# letter_i.net
KiCad netlist of a schematic drawn in EAGLE
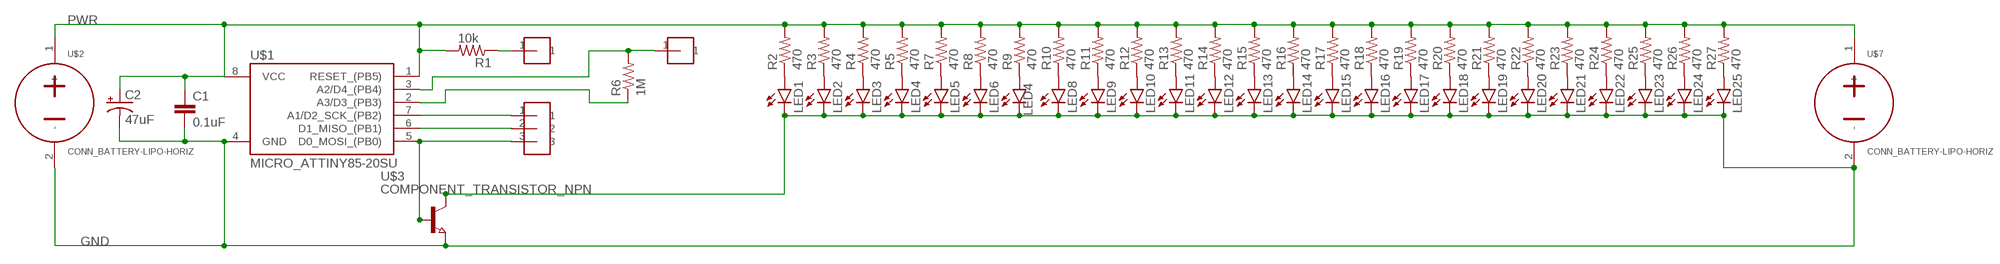
[diagram p0: schematic, sheet 1]

(export (version "E")
  (design (tool "Eeschema 10.0.6"))
  (components
    (comp (ref "C1")
      (value "0.1uF")
      (footprint "eagle-import:0805")
      (libsource (lib "eagle-import") (part "COMPONENT_CAP-0805"))
    )
    (comp (ref "C2")
      (value "47uF")
      (footprint "eagle-import:CAP_RADIAL_CAN_10MM")
      (libsource (lib "eagle-import") (part "COMPONENT_CAP_POL-6.3MM"))
    )
    (comp (ref "LED1")
      (value "LED-0805")
      (footprint "eagle-import:CHIP-LED0805")
      (libsource (lib "eagle-import") (part "LED-0805"))
    )
    (comp (ref "LED2")
      (value "LED-0805")
      (footprint "eagle-import:CHIP-LED0805")
      (libsource (lib "eagle-import") (part "LED-0805"))
    )
    (comp (ref "LED3")
      (value "LED-0805")
      (footprint "eagle-import:CHIP-LED0805")
      (libsource (lib "eagle-import") (part "LED-0805"))
    )
    (comp (ref "LED4")
      (value "LED-0805")
      (footprint "eagle-import:CHIP-LED0805")
      (libsource (lib "eagle-import") (part "LED-0805"))
    )
    (comp (ref "LED5")
      (value "LED-0805")
      (footprint "eagle-import:CHIP-LED0805")
      (libsource (lib "eagle-import") (part "LED-0805"))
    )
    (comp (ref "LED6")
      (value "LED-0805")
      (footprint "eagle-import:CHIP-LED0805")
      (libsource (lib "eagle-import") (part "LED-0805"))
    )
    (comp (ref "LED7")
      (value "LED-0805")
      (footprint "eagle-import:CHIP-LED0805")
      (libsource (lib "eagle-import") (part "LED-0805"))
    )
    (comp (ref "LED8")
      (value "LED-0805")
      (footprint "eagle-import:CHIP-LED0805")
      (libsource (lib "eagle-import") (part "LED-0805"))
    )
    (comp (ref "LED9")
      (value "LED-0805")
      (footprint "eagle-import:CHIP-LED0805")
      (libsource (lib "eagle-import") (part "LED-0805"))
    )
    (comp (ref "LED10")
      (value "LED-0805")
      (footprint "eagle-import:CHIP-LED0805")
      (libsource (lib "eagle-import") (part "LED-0805"))
    )
    (comp (ref "LED11")
      (value "LED-0805")
      (footprint "eagle-import:CHIP-LED0805")
      (libsource (lib "eagle-import") (part "LED-0805"))
    )
    (comp (ref "LED12")
      (value "LED-0805")
      (footprint "eagle-import:CHIP-LED0805")
      (libsource (lib "eagle-import") (part "LED-0805"))
    )
    (comp (ref "LED13")
      (value "LED-0805")
      (footprint "eagle-import:CHIP-LED0805")
      (libsource (lib "eagle-import") (part "LED-0805"))
    )
    (comp (ref "LED14")
      (value "LED-0805")
      (footprint "eagle-import:CHIP-LED0805")
      (libsource (lib "eagle-import") (part "LED-0805"))
    )
    (comp (ref "LED15")
      (value "LED-0805")
      (footprint "eagle-import:CHIP-LED0805")
      (libsource (lib "eagle-import") (part "LED-0805"))
    )
    (comp (ref "LED16")
      (value "LED-0805")
      (footprint "eagle-import:CHIP-LED0805")
      (libsource (lib "eagle-import") (part "LED-0805"))
    )
    (comp (ref "LED17")
      (value "LED-0805")
      (footprint "eagle-import:CHIP-LED0805")
      (libsource (lib "eagle-import") (part "LED-0805"))
    )
    (comp (ref "LED18")
      (value "LED-0805")
      (footprint "eagle-import:CHIP-LED0805")
      (libsource (lib "eagle-import") (part "LED-0805"))
    )
    (comp (ref "LED19")
      (value "LED-0805")
      (footprint "eagle-import:CHIP-LED0805")
      (libsource (lib "eagle-import") (part "LED-0805"))
    )
    (comp (ref "LED20")
      (value "LED-0805")
      (footprint "eagle-import:CHIP-LED0805")
      (libsource (lib "eagle-import") (part "LED-0805"))
    )
    (comp (ref "LED21")
      (value "LED-0805")
      (footprint "eagle-import:CHIP-LED0805")
      (libsource (lib "eagle-import") (part "LED-0805"))
    )
    (comp (ref "LED22")
      (value "LED-0805")
      (footprint "eagle-import:CHIP-LED0805")
      (libsource (lib "eagle-import") (part "LED-0805"))
    )
    (comp (ref "LED23")
      (value "LED-0805")
      (footprint "eagle-import:CHIP-LED0805")
      (libsource (lib "eagle-import") (part "LED-0805"))
    )
    (comp (ref "LED24")
      (value "LED-0805")
      (footprint "eagle-import:CHIP-LED0805")
      (libsource (lib "eagle-import") (part "LED-0805"))
    )
    (comp (ref "LED25")
      (value "LED-0805")
      (footprint "eagle-import:CHIP-LED0805")
      (libsource (lib "eagle-import") (part "LED-0805"))
    )
    (comp (ref "R1")
      (value "10k")
      (footprint "eagle-import:0805")
      (libsource (lib "eagle-import") (part "COMPONENT_RESISTOR-0805"))
    )
    (comp (ref "R2")
      (value "470")
      (footprint "eagle-import:0805")
      (libsource (lib "eagle-import") (part "COMPONENT_RESISTOR-0805"))
    )
    (comp (ref "R3")
      (value "470")
      (footprint "eagle-import:0805")
      (libsource (lib "eagle-import") (part "COMPONENT_RESISTOR-0805"))
    )
    (comp (ref "R4")
      (value "470")
      (footprint "eagle-import:0805")
      (libsource (lib "eagle-import") (part "COMPONENT_RESISTOR-0805"))
    )
    (comp (ref "R5")
      (value "470")
      (footprint "eagle-import:0805")
      (libsource (lib "eagle-import") (part "COMPONENT_RESISTOR-0805"))
    )
    (comp (ref "R6")
      (value "1M")
      (footprint "eagle-import:0805")
      (libsource (lib "eagle-import") (part "COMPONENT_RESISTOR-0805"))
    )
    (comp (ref "R7")
      (value "470")
      (footprint "eagle-import:0805")
      (libsource (lib "eagle-import") (part "COMPONENT_RESISTOR-0805"))
    )
    (comp (ref "R8")
      (value "470")
      (footprint "eagle-import:0805")
      (libsource (lib "eagle-import") (part "COMPONENT_RESISTOR-0805"))
    )
    (comp (ref "R9")
      (value "470")
      (footprint "eagle-import:0805")
      (libsource (lib "eagle-import") (part "COMPONENT_RESISTOR-0805"))
    )
    (comp (ref "R10")
      (value "470")
      (footprint "eagle-import:0805")
      (libsource (lib "eagle-import") (part "COMPONENT_RESISTOR-0805"))
    )
    (comp (ref "R11")
      (value "470")
      (footprint "eagle-import:0805")
      (libsource (lib "eagle-import") (part "COMPONENT_RESISTOR-0805"))
    )
    (comp (ref "R12")
      (value "470")
      (footprint "eagle-import:0805")
      (libsource (lib "eagle-import") (part "COMPONENT_RESISTOR-0805"))
    )
    (comp (ref "R13")
      (value "470")
      (footprint "eagle-import:0805")
      (libsource (lib "eagle-import") (part "COMPONENT_RESISTOR-0805"))
    )
    (comp (ref "R14")
      (value "470")
      (footprint "eagle-import:0805")
      (libsource (lib "eagle-import") (part "COMPONENT_RESISTOR-0805"))
    )
    (comp (ref "R15")
      (value "470")
      (footprint "eagle-import:0805")
      (libsource (lib "eagle-import") (part "COMPONENT_RESISTOR-0805"))
    )
    (comp (ref "R16")
      (value "470")
      (footprint "eagle-import:0805")
      (libsource (lib "eagle-import") (part "COMPONENT_RESISTOR-0805"))
    )
    (comp (ref "R17")
      (value "470")
      (footprint "eagle-import:0805")
      (libsource (lib "eagle-import") (part "COMPONENT_RESISTOR-0805"))
    )
    (comp (ref "R18")
      (value "470")
      (footprint "eagle-import:0805")
      (libsource (lib "eagle-import") (part "COMPONENT_RESISTOR-0805"))
    )
    (comp (ref "R19")
      (value "470")
      (footprint "eagle-import:0805")
      (libsource (lib "eagle-import") (part "COMPONENT_RESISTOR-0805"))
    )
    (comp (ref "R20")
      (value "470")
      (footprint "eagle-import:0805")
      (libsource (lib "eagle-import") (part "COMPONENT_RESISTOR-0805"))
    )
    (comp (ref "R21")
      (value "470")
      (footprint "eagle-import:0805")
      (libsource (lib "eagle-import") (part "COMPONENT_RESISTOR-0805"))
    )
    (comp (ref "R22")
      (value "470")
      (footprint "eagle-import:0805")
      (libsource (lib "eagle-import") (part "COMPONENT_RESISTOR-0805"))
    )
    (comp (ref "R23")
      (value "470")
      (footprint "eagle-import:0805")
      (libsource (lib "eagle-import") (part "COMPONENT_RESISTOR-0805"))
    )
    (comp (ref "R24")
      (value "470")
      (footprint "eagle-import:0805")
      (libsource (lib "eagle-import") (part "COMPONENT_RESISTOR-0805"))
    )
    (comp (ref "R25")
      (value "470")
      (footprint "eagle-import:0805")
      (libsource (lib "eagle-import") (part "COMPONENT_RESISTOR-0805"))
    )
    (comp (ref "R26")
      (value "470")
      (footprint "eagle-import:0805")
      (libsource (lib "eagle-import") (part "COMPONENT_RESISTOR-0805"))
    )
    (comp (ref "R27")
      (value "470")
      (footprint "eagle-import:0805")
      (libsource (lib "eagle-import") (part "COMPONENT_RESISTOR-0805"))
    )
    (comp (ref "U$1")
      (value "MICRO_ATTINY85-20SU")
      (footprint "eagle-import:SOIC8")
      (libsource (lib "eagle-import") (part "MICRO_ATTINY85-20SU"))
    )
    (comp (ref "U$2")
      (value "CONN_BATTERY-LIPO-HORIZ")
      (footprint "eagle-import:JST-PH-2-SMT-RA")
      (libsource (lib "eagle-import") (part "CONN_BATTERY-LIPO-HORIZ"))
    )
    (comp (ref "U$3")
      (value "COMPONENT_TRANSISTOR_NPN")
      (footprint "eagle-import:SOT23")
      (libsource (lib "eagle-import") (part "COMPONENT_TRANSISTOR_NPN"))
    )
    (comp (ref "U$4")
      (value "HEADER-1-TESTPOINT")
      (footprint "eagle-import:TESTPOINT-1")
      (libsource (lib "eagle-import") (part "HEADER-1-TESTPOINT"))
    )
    (comp (ref "U$5")
      (value "HEADER-1-TESTPOINT")
      (footprint "eagle-import:TESTPOINT-1")
      (libsource (lib "eagle-import") (part "HEADER-1-TESTPOINT"))
    )
    (comp (ref "U$6")
      (value "HEADER-3-TESTPOINT")
      (footprint "eagle-import:TESTPOINT-3")
      (libsource (lib "eagle-import") (part "HEADER-3-TESTPOINT"))
    )
    (comp (ref "U$7")
      (value "CONN_BATTERY-LIPO-HORIZ")
      (footprint "eagle-import:JST-PH-2-SMT-RA")
      (libsource (lib "eagle-import") (part "CONN_BATTERY-LIPO-HORIZ"))
    )
  )
  (nets
    (net (code "1") (name "/GND") (class "Default")
      (node (ref "C1") (pin "2") (pinfunction "2_2") (pintype "passive"))
      (node (ref "C2") (pin "-") (pinfunction "-_-") (pintype "passive"))
      (node (ref "LED1") (pin "C") (pinfunction "C_C") (pintype "passive"))
      (node (ref "LED10") (pin "C") (pinfunction "C_C") (pintype "passive"))
      (node (ref "LED11") (pin "C") (pinfunction "C_C") (pintype "passive"))
      (node (ref "LED12") (pin "C") (pinfunction "C_C") (pintype "passive"))
      (node (ref "LED13") (pin "C") (pinfunction "C_C") (pintype "passive"))
      (node (ref "LED14") (pin "C") (pinfunction "C_C") (pintype "passive"))
      (node (ref "LED15") (pin "C") (pinfunction "C_C") (pintype "passive"))
      (node (ref "LED16") (pin "C") (pinfunction "C_C") (pintype "passive"))
      (node (ref "LED17") (pin "C") (pinfunction "C_C") (pintype "passive"))
      (node (ref "LED18") (pin "C") (pinfunction "C_C") (pintype "passive"))
      (node (ref "LED19") (pin "C") (pinfunction "C_C") (pintype "passive"))
      (node (ref "LED2") (pin "C") (pinfunction "C_C") (pintype "passive"))
      (node (ref "LED20") (pin "C") (pinfunction "C_C") (pintype "passive"))
      (node (ref "LED21") (pin "C") (pinfunction "C_C") (pintype "passive"))
      (node (ref "LED22") (pin "C") (pinfunction "C_C") (pintype "passive"))
      (node (ref "LED23") (pin "C") (pinfunction "C_C") (pintype "passive"))
      (node (ref "LED24") (pin "C") (pinfunction "C_C") (pintype "passive"))
      (node (ref "LED25") (pin "C") (pinfunction "C_C") (pintype "passive"))
      (node (ref "LED3") (pin "C") (pinfunction "C_C") (pintype "passive"))
      (node (ref "LED4") (pin "C") (pinfunction "C_C") (pintype "passive"))
      (node (ref "LED5") (pin "C") (pinfunction "C_C") (pintype "passive"))
      (node (ref "LED6") (pin "C") (pinfunction "C_C") (pintype "passive"))
      (node (ref "LED7") (pin "C") (pinfunction "C_C") (pintype "passive"))
      (node (ref "LED8") (pin "C") (pinfunction "C_C") (pintype "passive"))
      (node (ref "LED9") (pin "C") (pinfunction "C_C") (pintype "passive"))
      (node (ref "U$1") (pin "4") (pinfunction "GND_4") (pintype "power_in"))
      (node (ref "U$2") (pin "2") (pinfunction "-_2") (pintype "bidirectional"))
      (node (ref "U$3") (pin "2") (pinfunction "E_2") (pintype "passive"))
      (node (ref "U$3") (pin "3") (pinfunction "C_3") (pintype "passive"))
      (node (ref "U$7") (pin "2") (pinfunction "-_2") (pintype "bidirectional"))
    )
    (net (code "2") (name "/PWR") (class "Default")
      (node (ref "C1") (pin "1") (pinfunction "1_1") (pintype "passive"))
      (node (ref "C2") (pin "+") (pinfunction "+_+") (pintype "passive"))
      (node (ref "R1") (pin "2") (pinfunction "2_2") (pintype "passive"))
      (node (ref "R10") (pin "2") (pinfunction "2_2") (pintype "passive"))
      (node (ref "R11") (pin "2") (pinfunction "2_2") (pintype "passive"))
      (node (ref "R12") (pin "2") (pinfunction "2_2") (pintype "passive"))
      (node (ref "R13") (pin "2") (pinfunction "2_2") (pintype "passive"))
      (node (ref "R14") (pin "2") (pinfunction "2_2") (pintype "passive"))
      (node (ref "R15") (pin "2") (pinfunction "2_2") (pintype "passive"))
      (node (ref "R16") (pin "2") (pinfunction "2_2") (pintype "passive"))
      (node (ref "R17") (pin "2") (pinfunction "2_2") (pintype "passive"))
      (node (ref "R18") (pin "2") (pinfunction "2_2") (pintype "passive"))
      (node (ref "R19") (pin "2") (pinfunction "2_2") (pintype "passive"))
      (node (ref "R2") (pin "2") (pinfunction "2_2") (pintype "passive"))
      (node (ref "R20") (pin "2") (pinfunction "2_2") (pintype "passive"))
      (node (ref "R21") (pin "2") (pinfunction "2_2") (pintype "passive"))
      (node (ref "R22") (pin "2") (pinfunction "2_2") (pintype "passive"))
      (node (ref "R23") (pin "2") (pinfunction "2_2") (pintype "passive"))
      (node (ref "R24") (pin "2") (pinfunction "2_2") (pintype "passive"))
      (node (ref "R25") (pin "2") (pinfunction "2_2") (pintype "passive"))
      (node (ref "R26") (pin "2") (pinfunction "2_2") (pintype "passive"))
      (node (ref "R27") (pin "2") (pinfunction "2_2") (pintype "passive"))
      (node (ref "R3") (pin "2") (pinfunction "2_2") (pintype "passive"))
      (node (ref "R4") (pin "2") (pinfunction "2_2") (pintype "passive"))
      (node (ref "R5") (pin "2") (pinfunction "2_2") (pintype "passive"))
      (node (ref "R7") (pin "2") (pinfunction "2_2") (pintype "passive"))
      (node (ref "R8") (pin "2") (pinfunction "2_2") (pintype "passive"))
      (node (ref "R9") (pin "2") (pinfunction "2_2") (pintype "passive"))
      (node (ref "U$1") (pin "1") (pinfunction "RESET_(PB5)_1") (pintype "bidirectional"))
      (node (ref "U$1") (pin "8") (pinfunction "VCC_8") (pintype "power_in"))
      (node (ref "U$2") (pin "1") (pinfunction "+_1") (pintype "bidirectional"))
      (node (ref "U$7") (pin "1") (pinfunction "+_1") (pintype "bidirectional"))
    )
    (net (code "3") (name "Net-(LED1-PadA)") (class "Default")
      (node (ref "LED1") (pin "A") (pinfunction "A_A") (pintype "passive"))
      (node (ref "R2") (pin "1") (pinfunction "1_1") (pintype "passive"))
    )
    (net (code "4") (name "Net-(LED2-PadA)") (class "Default")
      (node (ref "LED2") (pin "A") (pinfunction "A_A") (pintype "passive"))
      (node (ref "R3") (pin "1") (pinfunction "1_1") (pintype "passive"))
    )
    (net (code "5") (name "Net-(LED3-PadA)") (class "Default")
      (node (ref "LED3") (pin "A") (pinfunction "A_A") (pintype "passive"))
      (node (ref "R4") (pin "1") (pinfunction "1_1") (pintype "passive"))
    )
    (net (code "6") (name "Net-(LED4-PadA)") (class "Default")
      (node (ref "LED4") (pin "A") (pinfunction "A_A") (pintype "passive"))
      (node (ref "R5") (pin "1") (pinfunction "1_1") (pintype "passive"))
    )
    (net (code "7") (name "Net-(LED5-PadA)") (class "Default")
      (node (ref "LED5") (pin "A") (pinfunction "A_A") (pintype "passive"))
      (node (ref "R7") (pin "1") (pinfunction "1_1") (pintype "passive"))
    )
    (net (code "8") (name "Net-(LED6-PadA)") (class "Default")
      (node (ref "LED6") (pin "A") (pinfunction "A_A") (pintype "passive"))
      (node (ref "R8") (pin "1") (pinfunction "1_1") (pintype "passive"))
    )
    (net (code "9") (name "Net-(LED7-PadA)") (class "Default")
      (node (ref "LED7") (pin "A") (pinfunction "A_A") (pintype "passive"))
      (node (ref "R9") (pin "1") (pinfunction "1_1") (pintype "passive"))
    )
    (net (code "10") (name "Net-(LED8-PadA)") (class "Default")
      (node (ref "LED8") (pin "A") (pinfunction "A_A") (pintype "passive"))
      (node (ref "R10") (pin "1") (pinfunction "1_1") (pintype "passive"))
    )
    (net (code "11") (name "Net-(LED9-PadA)") (class "Default")
      (node (ref "LED9") (pin "A") (pinfunction "A_A") (pintype "passive"))
      (node (ref "R11") (pin "1") (pinfunction "1_1") (pintype "passive"))
    )
    (net (code "12") (name "Net-(LED10-PadA)") (class "Default")
      (node (ref "LED10") (pin "A") (pinfunction "A_A") (pintype "passive"))
      (node (ref "R12") (pin "1") (pinfunction "1_1") (pintype "passive"))
    )
    (net (code "13") (name "Net-(LED11-PadA)") (class "Default")
      (node (ref "LED11") (pin "A") (pinfunction "A_A") (pintype "passive"))
      (node (ref "R13") (pin "1") (pinfunction "1_1") (pintype "passive"))
    )
    (net (code "14") (name "Net-(LED12-PadA)") (class "Default")
      (node (ref "LED12") (pin "A") (pinfunction "A_A") (pintype "passive"))
      (node (ref "R14") (pin "1") (pinfunction "1_1") (pintype "passive"))
    )
    (net (code "15") (name "Net-(LED13-PadA)") (class "Default")
      (node (ref "LED13") (pin "A") (pinfunction "A_A") (pintype "passive"))
      (node (ref "R15") (pin "1") (pinfunction "1_1") (pintype "passive"))
    )
    (net (code "16") (name "Net-(LED14-PadA)") (class "Default")
      (node (ref "LED14") (pin "A") (pinfunction "A_A") (pintype "passive"))
      (node (ref "R16") (pin "1") (pinfunction "1_1") (pintype "passive"))
    )
    (net (code "17") (name "Net-(LED15-PadA)") (class "Default")
      (node (ref "LED15") (pin "A") (pinfunction "A_A") (pintype "passive"))
      (node (ref "R17") (pin "1") (pinfunction "1_1") (pintype "passive"))
    )
    (net (code "18") (name "Net-(LED16-PadA)") (class "Default")
      (node (ref "LED16") (pin "A") (pinfunction "A_A") (pintype "passive"))
      (node (ref "R18") (pin "1") (pinfunction "1_1") (pintype "passive"))
    )
    (net (code "19") (name "Net-(LED17-PadA)") (class "Default")
      (node (ref "LED17") (pin "A") (pinfunction "A_A") (pintype "passive"))
      (node (ref "R19") (pin "1") (pinfunction "1_1") (pintype "passive"))
    )
    (net (code "20") (name "Net-(LED18-PadA)") (class "Default")
      (node (ref "LED18") (pin "A") (pinfunction "A_A") (pintype "passive"))
      (node (ref "R20") (pin "1") (pinfunction "1_1") (pintype "passive"))
    )
    (net (code "21") (name "Net-(LED19-PadA)") (class "Default")
      (node (ref "LED19") (pin "A") (pinfunction "A_A") (pintype "passive"))
      (node (ref "R21") (pin "1") (pinfunction "1_1") (pintype "passive"))
    )
    (net (code "22") (name "Net-(LED20-PadA)") (class "Default")
      (node (ref "LED20") (pin "A") (pinfunction "A_A") (pintype "passive"))
      (node (ref "R22") (pin "1") (pinfunction "1_1") (pintype "passive"))
    )
    (net (code "23") (name "Net-(LED21-PadA)") (class "Default")
      (node (ref "LED21") (pin "A") (pinfunction "A_A") (pintype "passive"))
      (node (ref "R23") (pin "1") (pinfunction "1_1") (pintype "passive"))
    )
    (net (code "24") (name "Net-(LED22-PadA)") (class "Default")
      (node (ref "LED22") (pin "A") (pinfunction "A_A") (pintype "passive"))
      (node (ref "R24") (pin "1") (pinfunction "1_1") (pintype "passive"))
    )
    (net (code "25") (name "Net-(LED23-PadA)") (class "Default")
      (node (ref "LED23") (pin "A") (pinfunction "A_A") (pintype "passive"))
      (node (ref "R25") (pin "1") (pinfunction "1_1") (pintype "passive"))
    )
    (net (code "26") (name "Net-(LED24-PadA)") (class "Default")
      (node (ref "LED24") (pin "A") (pinfunction "A_A") (pintype "passive"))
      (node (ref "R26") (pin "1") (pinfunction "1_1") (pintype "passive"))
    )
    (net (code "27") (name "Net-(LED25-PadA)") (class "Default")
      (node (ref "LED25") (pin "A") (pinfunction "A_A") (pintype "passive"))
      (node (ref "R27") (pin "1") (pinfunction "1_1") (pintype "passive"))
    )
    (net (code "28") (name "Net-(R1-Pad1)") (class "Default")
      (node (ref "R1") (pin "1") (pinfunction "1_1") (pintype "passive"))
      (node (ref "U$5") (pin "1") (pinfunction "1_1") (pintype "bidirectional"))
    )
    (net (code "29") (name "Net-(U$1-A1{slash}D2_SCK_(PB2))") (class "Default")
      (node (ref "U$1") (pin "7") (pinfunction "A1/D2_SCK_(PB2)_7") (pintype "bidirectional"))
      (node (ref "U$6") (pin "1") (pinfunction "1_1") (pintype "bidirectional"))
    )
    (net (code "30") (name "Net-(U$1-A2{slash}D4_(PB4))") (class "Default")
      (node (ref "R6") (pin "2") (pinfunction "2_2") (pintype "passive"))
      (node (ref "U$1") (pin "3") (pinfunction "A2/D4_(PB4)_3") (pintype "bidirectional"))
      (node (ref "U$4") (pin "1") (pinfunction "1_1") (pintype "bidirectional"))
    )
    (net (code "31") (name "Net-(U$1-A3{slash}D3_(PB3))") (class "Default")
      (node (ref "R6") (pin "1") (pinfunction "1_1") (pintype "passive"))
      (node (ref "U$1") (pin "2") (pinfunction "A3/D3_(PB3)_2") (pintype "bidirectional"))
    )
    (net (code "32") (name "Net-(U$1-D0_MOSI_(PB0))") (class "Default")
      (node (ref "U$1") (pin "5") (pinfunction "D0_MOSI_(PB0)_5") (pintype "bidirectional"))
      (node (ref "U$3") (pin "1") (pinfunction "B_1") (pintype "passive"))
      (node (ref "U$6") (pin "3") (pinfunction "3_3") (pintype "bidirectional"))
    )
    (net (code "33") (name "Net-(U$1-D1_MISO_(PB1))") (class "Default")
      (node (ref "U$1") (pin "6") (pinfunction "D1_MISO_(PB1)_6") (pintype "bidirectional"))
      (node (ref "U$6") (pin "2") (pinfunction "2_2") (pintype "bidirectional"))
    )
  )
)
